# Fog_DRL_Cam.net
KiCad netlist of a schematic drawn in EAGLE
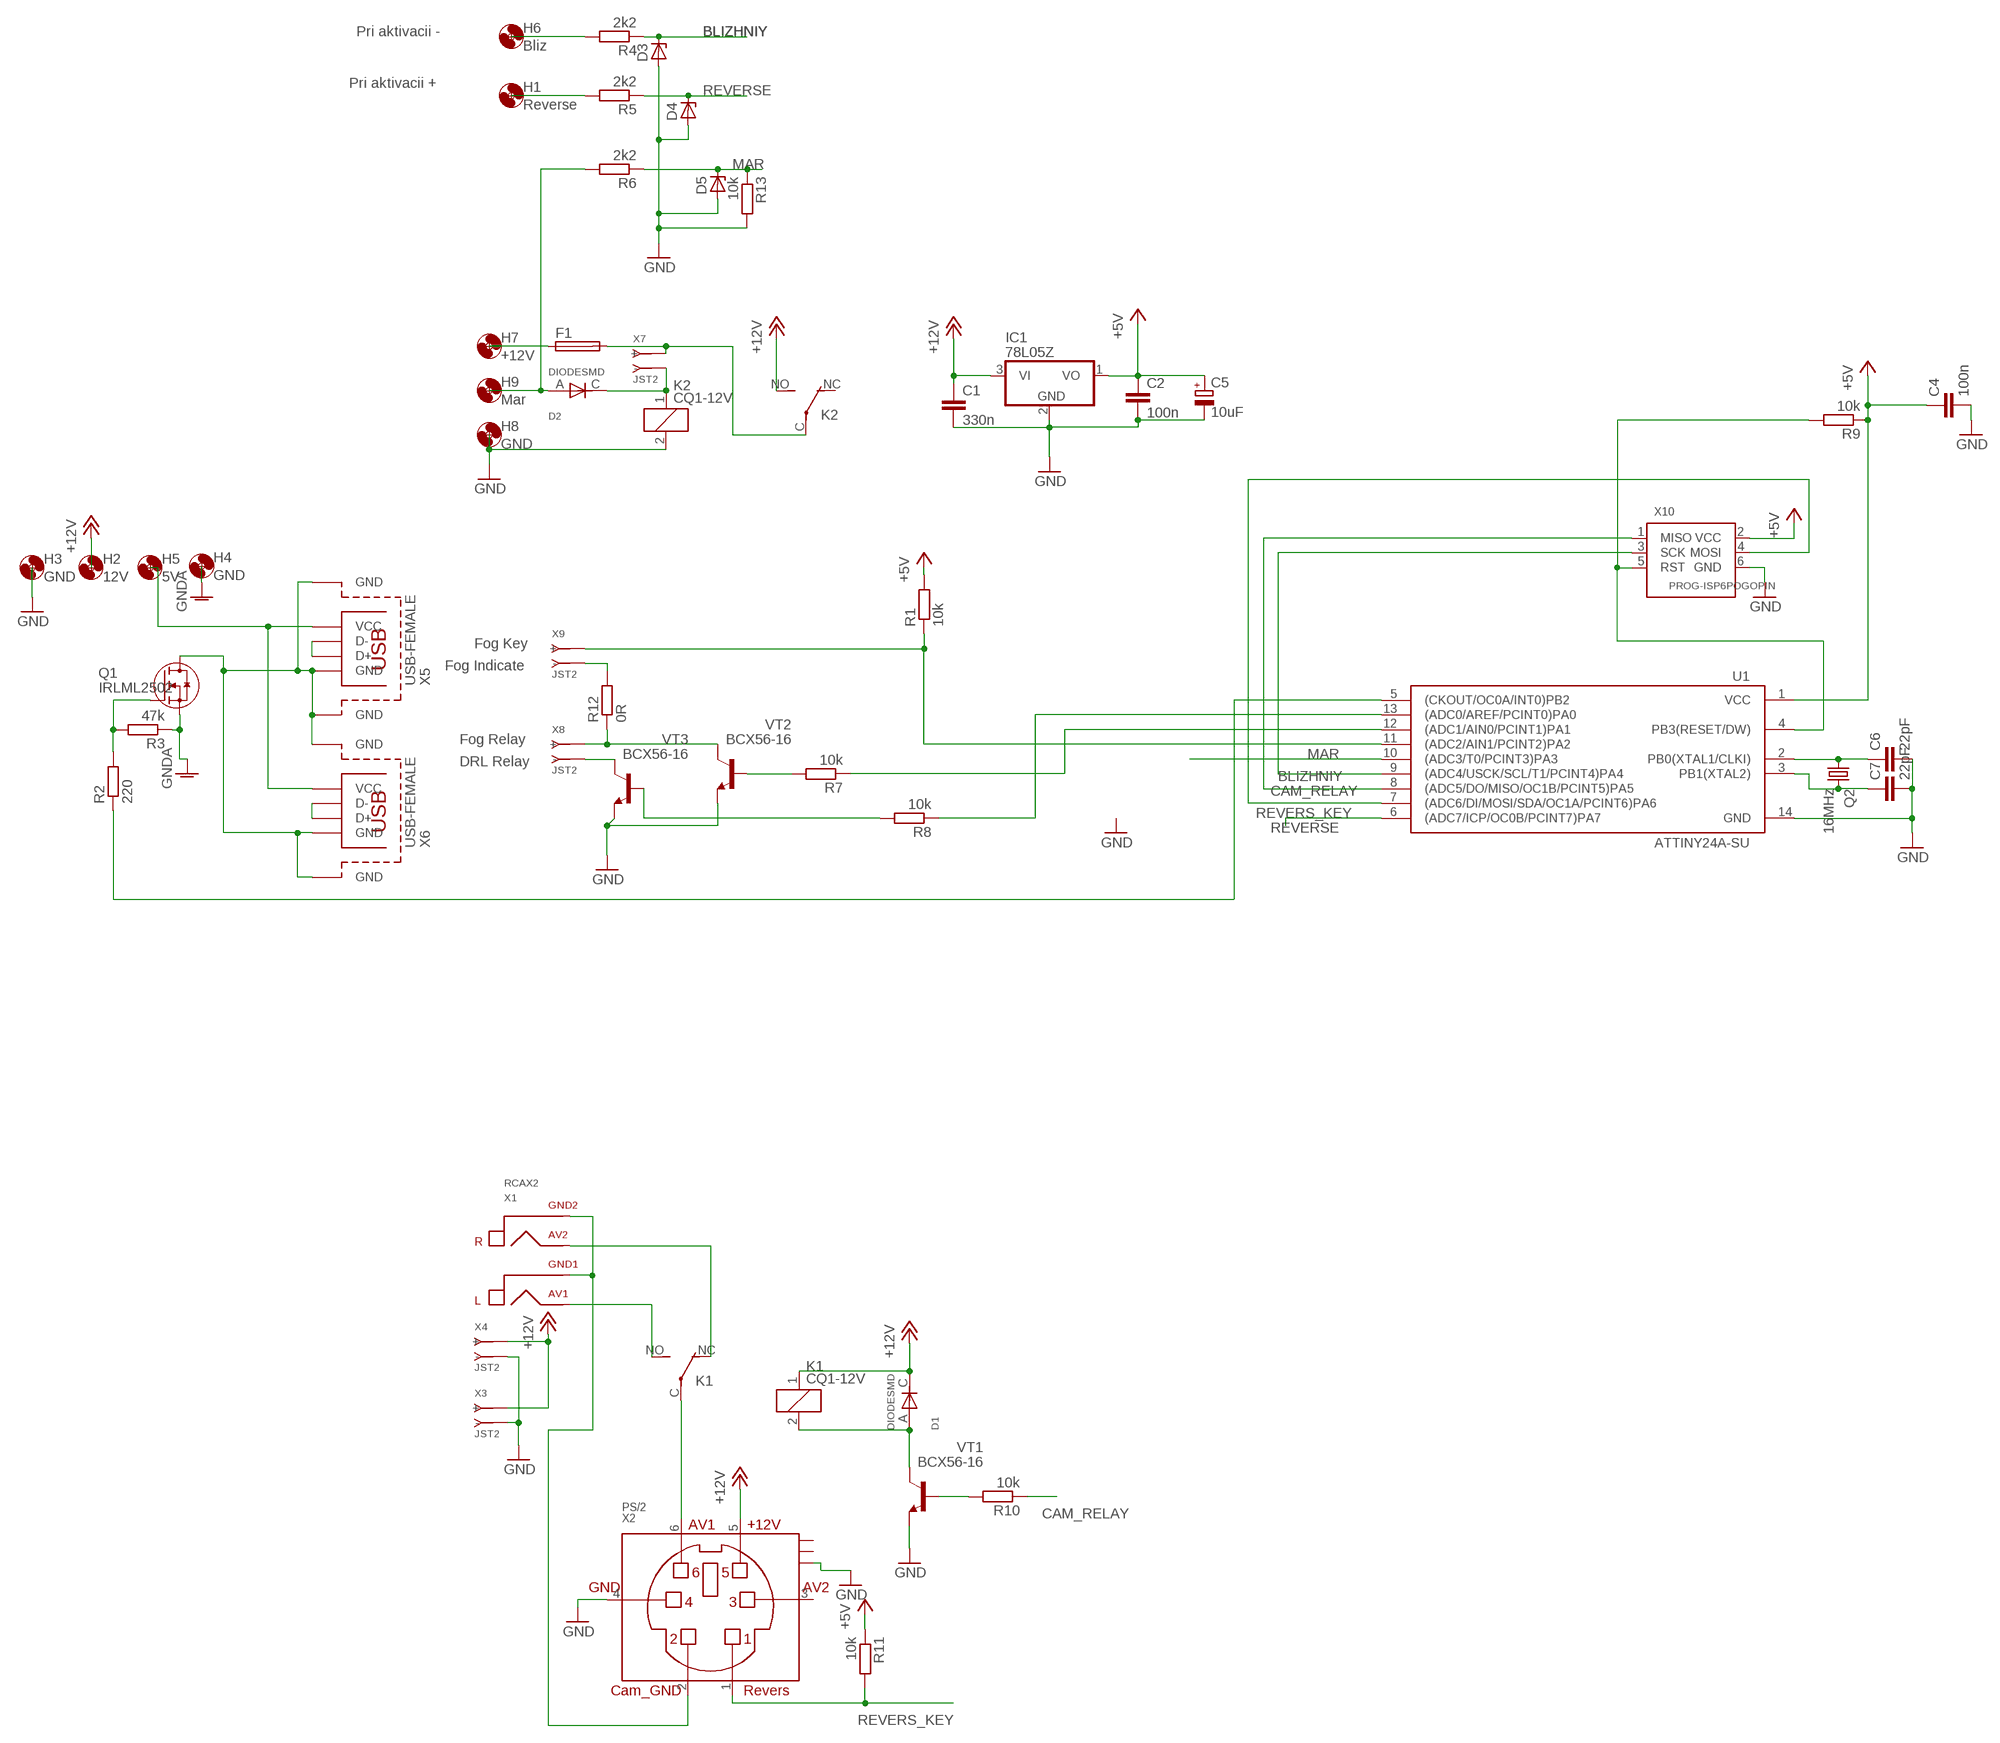
[diagram p0: schematic, sheet 1]

(export (version "E")
  (design (tool "Eeschema 10.0.6"))
  (components
    (comp (ref "C1")
      (value "330n")
      (footprint "eagle-import:C0805")
      (libsource (lib "eagle-import") (part "C-EUC0805"))
    )
    (comp (ref "C2")
      (value "100n")
      (footprint "eagle-import:C0603")
      (libsource (lib "eagle-import") (part "C-EUC0603"))
    )
    (comp (ref "C4")
      (value "100n")
      (footprint "eagle-import:C0603")
      (libsource (lib "eagle-import") (part "C-EUC0603"))
    )
    (comp (ref "C5")
      (value "10uF")
      (footprint "eagle-import:CT3216")
      (libsource (lib "eagle-import") (part "CPOL-EUCT3216"))
    )
    (comp (ref "C6")
      (value "22pF")
      (footprint "eagle-import:C0603")
      (libsource (lib "eagle-import") (part "rcl_334_C-EUC0603"))
    )
    (comp (ref "C7")
      (value "22pF")
      (footprint "eagle-import:C0603")
      (libsource (lib "eagle-import") (part "rcl_334_C-EUC0603"))
    )
    (comp (ref "D1")
      (value "DIODESMD")
      (footprint "eagle-import:DO214AC")
      (libsource (lib "eagle-import") (part "DIODESMD"))
    )
    (comp (ref "D2")
      (value "DIODESMD")
      (footprint "eagle-import:DO214AC")
      (libsource (lib "eagle-import") (part "DIODESMD"))
    )
    (comp (ref "D3")
      (value "ZENER-DIODESOD80C")
      (footprint "eagle-import:SOD80C")
      (libsource (lib "eagle-import") (part "ZENER-DIODESOD80C"))
    )
    (comp (ref "D4")
      (value "ZENER-DIODESOD80C")
      (footprint "eagle-import:SOD80C")
      (libsource (lib "eagle-import") (part "ZENER-DIODESOD80C"))
    )
    (comp (ref "D5")
      (value "ZENER-DIODESOD80C")
      (footprint "eagle-import:SOD80C")
      (libsource (lib "eagle-import") (part "ZENER-DIODESOD80C"))
    )
    (comp (ref "F1")
      (value "SH22,5A")
      (footprint "eagle-import:SH22,5A")
      (fields (field (name "MPN") "0031.7701.11"))
      (libsource (lib "eagle-import") (part "SH22,5A"))
    )
    (comp (ref "H1")
      (value "Reverse")
      (footprint "eagle-import:2,8")
      (libsource (lib "eagle-import") (part "MOUNT-HOLE2.8"))
    )
    (comp (ref "H2")
      (value "12V")
      (footprint "eagle-import:3,0")
      (libsource (lib "eagle-import") (part "MOUNT-HOLE3.0"))
    )
    (comp (ref "H3")
      (value "GND")
      (footprint "eagle-import:3,0")
      (libsource (lib "eagle-import") (part "MOUNT-HOLE3.0"))
    )
    (comp (ref "H4")
      (value "GND")
      (footprint "eagle-import:3,0")
      (libsource (lib "eagle-import") (part "MOUNT-HOLE3.0"))
    )
    (comp (ref "H5")
      (value "5V")
      (footprint "eagle-import:3,0")
      (libsource (lib "eagle-import") (part "MOUNT-HOLE3.0"))
    )
    (comp (ref "H6")
      (value "Bliz")
      (footprint "eagle-import:2,8")
      (libsource (lib "eagle-import") (part "MOUNT-HOLE2.8"))
    )
    (comp (ref "H7")
      (value "+12V")
      (footprint "eagle-import:3,0")
      (libsource (lib "eagle-import") (part "MOUNT-HOLE3.0"))
    )
    (comp (ref "H8")
      (value "GND")
      (footprint "eagle-import:3,0")
      (libsource (lib "eagle-import") (part "MOUNT-HOLE3.0"))
    )
    (comp (ref "H9")
      (value "Mar")
      (footprint "eagle-import:2,8")
      (libsource (lib "eagle-import") (part "MOUNT-HOLE2.8"))
    )
    (comp (ref "IC1")
      (value "78L05Z")
      (footprint "eagle-import:TO92")
      (libsource (lib "eagle-import") (part "78ZL05"))
    )
    (comp (ref "K1")
      (value "CQ1-12V")
      (footprint "eagle-import:CQ1")
      (libsource (lib "eagle-import") (part "CQ1-12V"))
    )
    (comp (ref "K2")
      (value "CQ1-12V")
      (footprint "eagle-import:CQ1")
      (libsource (lib "eagle-import") (part "CQ1-12V"))
    )
    (comp (ref "Q1")
      (value "IRLML2502")
      (footprint "eagle-import:SOT-23-GSD")
      (libsource (lib "eagle-import") (part "SI2302"))
    )
    (comp (ref "Q2")
      (value "16MHz")
      (footprint "eagle-import:HC49UP")
      (libsource (lib "eagle-import") (part "CRYSTALHC49UP"))
    )
    (comp (ref "R1")
      (value "10k")
      (footprint "eagle-import:R0603")
      (libsource (lib "eagle-import") (part "R-EU_R0603"))
    )
    (comp (ref "R2")
      (value "220")
      (footprint "eagle-import:R0603")
      (libsource (lib "eagle-import") (part "R-EU_R0603"))
    )
    (comp (ref "R3")
      (value "47k")
      (footprint "eagle-import:R0603")
      (libsource (lib "eagle-import") (part "R-EU_R0603"))
    )
    (comp (ref "R4")
      (value "2k2")
      (footprint "eagle-import:R0603")
      (libsource (lib "eagle-import") (part "R-EU_R0603"))
    )
    (comp (ref "R5")
      (value "2k2")
      (footprint "eagle-import:R0603")
      (libsource (lib "eagle-import") (part "R-EU_R0603"))
    )
    (comp (ref "R6")
      (value "2k2")
      (footprint "eagle-import:R0603")
      (libsource (lib "eagle-import") (part "R-EU_R0603"))
    )
    (comp (ref "R7")
      (value "10k")
      (footprint "eagle-import:R0603")
      (libsource (lib "eagle-import") (part "R-EU_R0603"))
    )
    (comp (ref "R8")
      (value "10k")
      (footprint "eagle-import:R0603")
      (libsource (lib "eagle-import") (part "R-EU_R0603"))
    )
    (comp (ref "R9")
      (value "10k")
      (footprint "eagle-import:R0603")
      (libsource (lib "eagle-import") (part "R-EU_R0603"))
    )
    (comp (ref "R10")
      (value "10k")
      (footprint "eagle-import:R0603")
      (libsource (lib "eagle-import") (part "R-EU_R0603"))
    )
    (comp (ref "R11")
      (value "10k")
      (footprint "eagle-import:R0603")
      (libsource (lib "eagle-import") (part "R-EU_R0603"))
    )
    (comp (ref "R12")
      (value "0R")
      (footprint "eagle-import:R0603")
      (libsource (lib "eagle-import") (part "R-EU_R0603"))
    )
    (comp (ref "R13")
      (value "10k")
      (footprint "eagle-import:R0603")
      (libsource (lib "eagle-import") (part "R-EU_R0603"))
    )
    (comp (ref "U1")
      (value "ATTINY24A-SU")
      (footprint "eagle-import:SO14")
      (libsource (lib "eagle-import") (part "ATTINY24A-SU"))
    )
    (comp (ref "VT1")
      (value "BCX56-16")
      (footprint "eagle-import:SOT89-BCE")
      (libsource (lib "eagle-import") (part "BCX56-16"))
    )
    (comp (ref "VT2")
      (value "BCX56-16")
      (footprint "eagle-import:SOT89-BCE")
      (libsource (lib "eagle-import") (part "BCX56-16"))
    )
    (comp (ref "VT3")
      (value "BCX56-16")
      (footprint "eagle-import:SOT89-BCE")
      (libsource (lib "eagle-import") (part "BCX56-16"))
    )
    (comp (ref "X1")
      (value "RCAX2")
      (footprint "eagle-import:RCAX2")
      (libsource (lib "eagle-import") (part "RCAX2"))
    )
    (comp (ref "X2")
      (value "PS/2")
      (footprint "eagle-import:PS_2")
      (libsource (lib "eagle-import") (part "PS/2"))
    )
    (comp (ref "X3")
      (value "JST2")
      (footprint "eagle-import:JST_2")
      (libsource (lib "eagle-import") (part "JST2"))
    )
    (comp (ref "X4")
      (value "JST2")
      (footprint "eagle-import:JST_2")
      (libsource (lib "eagle-import") (part "JST2"))
    )
    (comp (ref "X5")
      (value "USB-FEMALE")
      (footprint "eagle-import:USB-FEMALE")
      (libsource (lib "eagle-import") (part "USB-FEMALE"))
    )
    (comp (ref "X6")
      (value "USB-FEMALE")
      (footprint "eagle-import:USB-FEMALE")
      (libsource (lib "eagle-import") (part "USB-FEMALE"))
    )
    (comp (ref "X7")
      (value "JST2")
      (footprint "eagle-import:JST_2")
      (libsource (lib "eagle-import") (part "JST2"))
    )
    (comp (ref "X8")
      (value "JST2")
      (footprint "eagle-import:JST_2")
      (libsource (lib "eagle-import") (part "JST2"))
    )
    (comp (ref "X9")
      (value "JST2")
      (footprint "eagle-import:JST_2")
      (libsource (lib "eagle-import") (part "JST2"))
    )
    (comp (ref "X10")
      (value "PROG-ISP6POGOPIN")
      (footprint "eagle-import:PROG_POGOPIN")
      (libsource (lib "eagle-import") (part "PROG-ISP6POGOPIN"))
    )
  )
  (nets
    (net (code "1") (name "+5V") (class "Default")
      (node (ref "C2") (pin "1") (pinfunction "1_1") (pintype "passive"))
      (node (ref "C4") (pin "1") (pinfunction "1_1") (pintype "passive"))
      (node (ref "C5") (pin "+") (pinfunction "+_+") (pintype "passive"))
      (node (ref "IC1") (pin "1") (pinfunction "VO_1") (pintype "passive"))
      (node (ref "R1") (pin "2") (pinfunction "2_2") (pintype "passive"))
      (node (ref "R11") (pin "1") (pinfunction "1_1") (pintype "passive"))
      (node (ref "R9") (pin "1") (pinfunction "1_1") (pintype "passive"))
      (node (ref "U1") (pin "1") (pinfunction "VCC_1") (pintype "power_in"))
      (node (ref "X10") (pin "2") (pinfunction "VCC_2") (pintype "bidirectional"))
    )
    (net (code "2") (name "+12V") (class "Default")
      (node (ref "C1") (pin "1") (pinfunction "1_1") (pintype "passive"))
      (node (ref "D1") (pin "C") (pinfunction "KATOD_C") (pintype "power_in"))
      (node (ref "H2") (pin "P$1") (pinfunction "P$1_P$1") (pintype "bidirectional"))
      (node (ref "IC1") (pin "3") (pinfunction "VI_3") (pintype "input"))
      (node (ref "K1") (pin "1") (pinfunction "1_1") (pintype "passive"))
      (node (ref "K2") (pin "NO") (pinfunction "S_NO") (pintype "passive"))
      (node (ref "X2") (pin "5") (pinfunction "5_5") (pintype "bidirectional"))
      (node (ref "X3") (pin "1") (pinfunction "+_1") (pintype "bidirectional"))
      (node (ref "X4") (pin "1") (pinfunction "+_1") (pintype "bidirectional"))
    )
    (net (code "3") (name "/BLIZHNIY") (class "Default")
      (node (ref "D3") (pin "C") (pinfunction "C_C") (pintype "passive"))
      (node (ref "R4") (pin "1") (pinfunction "1_1") (pintype "passive"))
      (node (ref "U1") (pin "9") (pinfunction "(ADC4/USCK/SCL/T1/PCINT4)PA4_9") (pintype "bidirectional"))
      (node (ref "X10") (pin "3") (pinfunction "SCK_3") (pintype "bidirectional"))
    )
    (net (code "4") (name "/CAM_RELAY") (class "Default")
      (node (ref "R10") (pin "1") (pinfunction "1_1") (pintype "passive"))
      (node (ref "U1") (pin "8") (pinfunction "(ADC5/DO/MISO/OC1B/PCINT5)PA5_8") (pintype "bidirectional"))
      (node (ref "X10") (pin "1") (pinfunction "MISO_1") (pintype "bidirectional"))
    )
    (net (code "5") (name "/MAR") (class "Default")
      (node (ref "D5") (pin "C") (pinfunction "C_C") (pintype "passive"))
      (node (ref "R13") (pin "1") (pinfunction "1_1") (pintype "passive"))
      (node (ref "R6") (pin "1") (pinfunction "1_1") (pintype "passive"))
      (node (ref "U1") (pin "10") (pinfunction "(ADC3/T0/PCINT3)PA3_10") (pintype "bidirectional"))
    )
    (net (code "6") (name "/REVERSE") (class "Default")
      (node (ref "D4") (pin "C") (pinfunction "C_C") (pintype "passive"))
      (node (ref "R5") (pin "1") (pinfunction "1_1") (pintype "passive"))
      (node (ref "U1") (pin "6") (pinfunction "(ADC7/ICP/OC0B/PCINT7)PA7_6") (pintype "bidirectional"))
    )
    (net (code "7") (name "/REVERS_KEY") (class "Default")
      (node (ref "R11") (pin "2") (pinfunction "2_2") (pintype "passive"))
      (node (ref "U1") (pin "7") (pinfunction "(ADC6/DI/MOSI/SDA/OC1A/PCINT6)PA6_7") (pintype "bidirectional"))
      (node (ref "X10") (pin "4") (pinfunction "MOSI_4") (pintype "bidirectional"))
      (node (ref "X2") (pin "1") (pinfunction "1_1") (pintype "bidirectional"))
    )
    (net (code "8") (name "GND") (class "Default")
      (node (ref "C1") (pin "2") (pinfunction "2_2") (pintype "passive"))
      (node (ref "C2") (pin "2") (pinfunction "2_2") (pintype "passive"))
      (node (ref "C4") (pin "2") (pinfunction "2_2") (pintype "passive"))
      (node (ref "C5") (pin "-") (pinfunction "-_-") (pintype "passive"))
      (node (ref "C6") (pin "2") (pinfunction "2_2") (pintype "passive"))
      (node (ref "C7") (pin "2") (pinfunction "2_2") (pintype "passive"))
      (node (ref "D3") (pin "A") (pinfunction "A_A") (pintype "passive"))
      (node (ref "D4") (pin "A") (pinfunction "A_A") (pintype "passive"))
      (node (ref "D5") (pin "A") (pinfunction "A_A") (pintype "passive"))
      (node (ref "H3") (pin "P$1") (pinfunction "P$1_P$1") (pintype "bidirectional"))
      (node (ref "H8") (pin "P$1") (pinfunction "P$1_P$1") (pintype "bidirectional"))
      (node (ref "IC1") (pin "2") (pinfunction "GND_2") (pintype "passive"))
      (node (ref "K2") (pin "2") (pinfunction "2_2") (pintype "passive"))
      (node (ref "R13") (pin "2") (pinfunction "2_2") (pintype "passive"))
      (node (ref "U1") (pin "14") (pinfunction "GND_14") (pintype "power_in"))
      (node (ref "VT1") (pin "E") (pinfunction "E_E") (pintype "passive"))
      (node (ref "VT2") (pin "E") (pinfunction "E_E") (pintype "passive"))
      (node (ref "VT3") (pin "E") (pinfunction "E_E") (pintype "passive"))
      (node (ref "X10") (pin "6") (pinfunction "GND_6") (pintype "power_in"))
      (node (ref "X2") (pin "4") (pinfunction "4_4") (pintype "bidirectional"))
      (node (ref "X2") (pin "GND0") (pinfunction "GND0_GND0") (pintype "bidirectional"))
      (node (ref "X3") (pin "2") (pinfunction "-_2") (pintype "bidirectional"))
      (node (ref "X4") (pin "2") (pinfunction "-_2") (pintype "bidirectional"))
    )
    (net (code "9") (name "GNDA") (class "Default")
      (node (ref "H4") (pin "P$1") (pinfunction "P$1_P$1") (pintype "bidirectional"))
      (node (ref "Q1") (pin "S") (pinfunction "S_S") (pintype "passive"))
      (node (ref "R3") (pin "1") (pinfunction "1_1") (pintype "passive"))
    )
    (net (code "10") (name "Net-(D1-ANOD)") (class "Default")
      (node (ref "D1") (pin "A") (pinfunction "ANOD_A") (pintype "power_in"))
      (node (ref "K1") (pin "2") (pinfunction "2_2") (pintype "passive"))
      (node (ref "VT1") (pin "C") (pinfunction "C_C") (pintype "passive"))
      (node (ref "VT1") (pin "C@1") (pinfunction "C_C@1") (pintype "passive"))
    )
    (net (code "11") (name "Net-(D2-ANOD)") (class "Default")
      (node (ref "D2") (pin "A") (pinfunction "ANOD_A") (pintype "power_in"))
      (node (ref "H9") (pin "P$1") (pinfunction "P$1_P$1") (pintype "bidirectional"))
      (node (ref "R6") (pin "2") (pinfunction "2_2") (pintype "passive"))
    )
    (net (code "12") (name "Net-(D2-KATOD)") (class "Default")
      (node (ref "D2") (pin "C") (pinfunction "KATOD_C") (pintype "power_in"))
      (node (ref "K2") (pin "1") (pinfunction "1_1") (pintype "passive"))
      (node (ref "X7") (pin "2") (pinfunction "-_2") (pintype "bidirectional"))
    )
    (net (code "13") (name "Net-(F1-Pad1)") (class "Default")
      (node (ref "F1") (pin "1") (pinfunction "1_1") (pintype "passive"))
      (node (ref "H7") (pin "P$1") (pinfunction "P$1_P$1") (pintype "bidirectional"))
    )
    (net (code "14") (name "Net-(H1-PadP$1)") (class "Default")
      (node (ref "H1") (pin "P$1") (pinfunction "P$1_P$1") (pintype "bidirectional"))
      (node (ref "R5") (pin "2") (pinfunction "2_2") (pintype "passive"))
    )
    (net (code "15") (name "Net-(H5-PadP$1)") (class "Default")
      (node (ref "H5") (pin "P$1") (pinfunction "P$1_P$1") (pintype "bidirectional"))
      (node (ref "X5") (pin "VCC") (pinfunction "VCC_VCC") (pintype "power_in"))
      (node (ref "X6") (pin "VCC") (pinfunction "VCC_VCC") (pintype "power_in"))
    )
    (net (code "16") (name "Net-(H6-PadP$1)") (class "Default")
      (node (ref "H6") (pin "P$1") (pinfunction "P$1_P$1") (pintype "bidirectional"))
      (node (ref "R4") (pin "2") (pinfunction "2_2") (pintype "passive"))
    )
    (net (code "17") (name "Net-(K1B-O)") (class "Default")
      (node (ref "K1") (pin "NC") (pinfunction "O_NC") (pintype "passive"))
      (node (ref "X1") (pin "AV2") (pinfunction "AV2_AV2") (pintype "bidirectional"))
    )
    (net (code "18") (name "Net-(K1B-P)") (class "Default")
      (node (ref "K1") (pin "C") (pinfunction "P_C") (pintype "passive"))
      (node (ref "X2") (pin "6") (pinfunction "6_6") (pintype "bidirectional"))
    )
    (net (code "19") (name "Net-(K1B-S)") (class "Default")
      (node (ref "K1") (pin "NO") (pinfunction "S_NO") (pintype "passive"))
      (node (ref "X1") (pin "AV1") (pinfunction "AV1_AV1") (pintype "bidirectional"))
    )
    (net (code "20") (name "Net-(K2B-P)") (class "Default")
      (node (ref "F1") (pin "2") (pinfunction "2_2") (pintype "passive"))
      (node (ref "K2") (pin "C") (pinfunction "P_C") (pintype "passive"))
      (node (ref "X7") (pin "1") (pinfunction "+_1") (pintype "bidirectional"))
    )
    (net (code "21") (name "Net-(Q1-PadD)") (class "Default")
      (node (ref "Q1") (pin "D") (pinfunction "D_D") (pintype "passive"))
      (node (ref "X5") (pin "GND") (pinfunction "GND_GND") (pintype "power_in"))
      (node (ref "X5") (pin "GND@1") (pinfunction "GND_GND@1") (pintype "power_in"))
      (node (ref "X5") (pin "GND@2") (pinfunction "GND_GND@2") (pintype "power_in"))
      (node (ref "X6") (pin "GND") (pinfunction "GND_GND") (pintype "power_in"))
      (node (ref "X6") (pin "GND@1") (pinfunction "GND_GND@1") (pintype "power_in"))
      (node (ref "X6") (pin "GND@2") (pinfunction "GND_GND@2") (pintype "power_in"))
    )
    (net (code "22") (name "Net-(Q1-PadG)") (class "Default")
      (node (ref "Q1") (pin "G") (pinfunction "G_G") (pintype "passive"))
      (node (ref "R2") (pin "2") (pinfunction "2_2") (pintype "passive"))
      (node (ref "R3") (pin "2") (pinfunction "2_2") (pintype "passive"))
    )
    (net (code "23") (name "Net-(R7-Pad2)") (class "Default")
      (node (ref "R7") (pin "2") (pinfunction "2_2") (pintype "passive"))
      (node (ref "VT2") (pin "B") (pinfunction "B_B") (pintype "passive"))
    )
    (net (code "24") (name "Net-(R8-Pad2)") (class "Default")
      (node (ref "R8") (pin "2") (pinfunction "2_2") (pintype "passive"))
      (node (ref "VT3") (pin "B") (pinfunction "B_B") (pintype "passive"))
    )
    (net (code "25") (name "Net-(R10-Pad2)") (class "Default")
      (node (ref "R10") (pin "2") (pinfunction "2_2") (pintype "passive"))
      (node (ref "VT1") (pin "B") (pinfunction "B_B") (pintype "passive"))
    )
    (net (code "26") (name "Net-(U1-(ADC0{slash}AREF{slash}PCINT0)PA0)") (class "Default")
      (node (ref "R8") (pin "1") (pinfunction "1_1") (pintype "passive"))
      (node (ref "U1") (pin "13") (pinfunction "(ADC0/AREF/PCINT0)PA0_13") (pintype "bidirectional"))
    )
    (net (code "27") (name "Net-(U1-(ADC1{slash}AIN0{slash}PCINT1)PA1)") (class "Default")
      (node (ref "R7") (pin "1") (pinfunction "1_1") (pintype "passive"))
      (node (ref "U1") (pin "12") (pinfunction "(ADC1/AIN0/PCINT1)PA1_12") (pintype "bidirectional"))
    )
    (net (code "28") (name "Net-(U1-(ADC2{slash}AIN1{slash}PCINT2)PA2)") (class "Default")
      (node (ref "R1") (pin "1") (pinfunction "1_1") (pintype "passive"))
      (node (ref "U1") (pin "11") (pinfunction "(ADC2/AIN1/PCINT2)PA2_11") (pintype "bidirectional"))
      (node (ref "X9") (pin "1") (pinfunction "+_1") (pintype "bidirectional"))
    )
    (net (code "29") (name "Net-(U1-(CKOUT{slash}OC0A{slash}INT0)PB2)") (class "Default")
      (node (ref "R2") (pin "1") (pinfunction "1_1") (pintype "passive"))
      (node (ref "U1") (pin "5") (pinfunction "(CKOUT/OC0A/INT0)PB2_5") (pintype "bidirectional"))
    )
    (net (code "30") (name "Net-(U1-PB0(XTAL1{slash}CLKI))") (class "Default")
      (node (ref "C6") (pin "1") (pinfunction "1_1") (pintype "passive"))
      (node (ref "Q2") (pin "1") (pinfunction "1_1") (pintype "passive"))
      (node (ref "U1") (pin "2") (pinfunction "PB0(XTAL1/CLKI)_2") (pintype "bidirectional"))
    )
    (net (code "31") (name "Net-(U1-PB1(XTAL2))") (class "Default")
      (node (ref "C7") (pin "1") (pinfunction "1_1") (pintype "passive"))
      (node (ref "Q2") (pin "2") (pinfunction "2_2") (pintype "passive"))
      (node (ref "U1") (pin "3") (pinfunction "PB1(XTAL2)_3") (pintype "bidirectional"))
    )
    (net (code "32") (name "Net-(U1-PB3(RESET{slash}DW))") (class "Default")
      (node (ref "R9") (pin "2") (pinfunction "2_2") (pintype "passive"))
      (node (ref "U1") (pin "4") (pinfunction "PB3(RESET/DW)_4") (pintype "bidirectional"))
      (node (ref "X10") (pin "5") (pinfunction "RST_5") (pintype "bidirectional"))
    )
    (net (code "33") (name "Net-(X1-PadGND1)") (class "Default")
      (node (ref "X1") (pin "GND1") (pinfunction "GND1_GND1") (pintype "bidirectional"))
      (node (ref "X1") (pin "GND2") (pinfunction "GND2_GND2") (pintype "bidirectional"))
      (node (ref "X2") (pin "2") (pinfunction "2_2") (pintype "bidirectional"))
    )
    (net (code "34") (name "Net-(X5-PadD+)") (class "Default")
      (node (ref "X5") (pin "D+") (pinfunction "D+_D+") (pintype "bidirectional"))
      (node (ref "X5") (pin "D-") (pinfunction "D-_D-") (pintype "bidirectional"))
    )
    (net (code "35") (name "Net-(X6-PadD+)") (class "Default")
      (node (ref "X6") (pin "D+") (pinfunction "D+_D+") (pintype "bidirectional"))
      (node (ref "X6") (pin "D-") (pinfunction "D-_D-") (pintype "bidirectional"))
    )
    (net (code "36") (name "Net-(X8-+)") (class "Default")
      (node (ref "R12") (pin "1") (pinfunction "1_1") (pintype "passive"))
      (node (ref "VT2") (pin "C") (pinfunction "C_C") (pintype "passive"))
      (node (ref "VT2") (pin "C@1") (pinfunction "C_C@1") (pintype "passive"))
      (node (ref "X8") (pin "1") (pinfunction "+_1") (pintype "bidirectional"))
    )
    (net (code "37") (name "Net-(X8--)") (class "Default")
      (node (ref "VT3") (pin "C") (pinfunction "C_C") (pintype "passive"))
      (node (ref "VT3") (pin "C@1") (pinfunction "C_C@1") (pintype "passive"))
      (node (ref "X8") (pin "2") (pinfunction "-_2") (pintype "bidirectional"))
    )
    (net (code "38") (name "Net-(X9--)") (class "Default")
      (node (ref "R12") (pin "2") (pinfunction "2_2") (pintype "passive"))
      (node (ref "X9") (pin "2") (pinfunction "-_2") (pintype "bidirectional"))
    )
    (net (code "39") (name "unconnected-(K2B-O-PadNC)") (class "Default")
      (node (ref "K2") (pin "NC") (pinfunction "O_NC") (pintype "passive"))
    )
    (net (code "40") (name "unconnected-(X2-Pad3)") (class "Default")
      (node (ref "X2") (pin "3") (pinfunction "3_3") (pintype "bidirectional"))
    )
    (net (code "41") (name "unconnected-(X2-PadGND1)") (class "Default")
      (node (ref "X2") (pin "GND1") (pinfunction "GND1_GND1") (pintype "bidirectional"))
    )
    (net (code "42") (name "unconnected-(X2-PadGND2)") (class "Default")
      (node (ref "X2") (pin "GND2") (pinfunction "GND2_GND2") (pintype "bidirectional"))
    )
  )
)
